# Reference_Voltage_1V65.net
KiCad netlist of a schematic drawn in Altium Designer
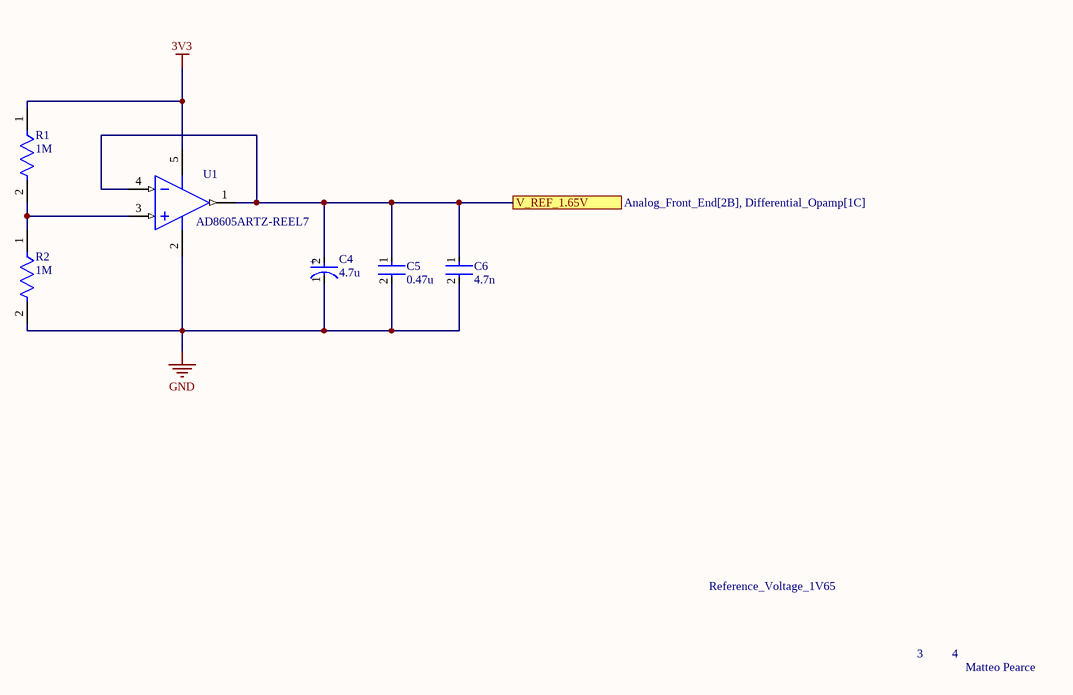
[diagram p0: Reference_Voltage_1V65.SchDoc]

(export (version "E")
  (design (tool "Eeschema 10.0.6"))
  (components
    (comp (ref "C4")
      (value "4.7u")
      (footprint "FP-TAJA-MFG")
      (description "4.7uF 20V  ±10% 4Ω 1206  SMD Tantalum Capacitor")
      (fields (field (name "TOLERANCE") "10%") (field (name "VOLTAGE") "20V"))
      (libsource (lib "Altium Content Vault") (part "203bc49f2ac43e59fd269a8c329ed05"))
    )
    (comp (ref "C5")
      (value "0.47u")
      (footprint "FP-GCM188-0_1-IPC_A")
      (description "Ceramic Capacitor for Automotive 470nF  ±10% 16VDC X7R 0603 Paper T/R")
      (fields (field (name "VOLTAGE") "16V") (field (name "TOLERANCE") "10%"))
      (libsource (lib "Altium Content Vault") (part "02cd4be3c70576c341d710602a673aa"))
    )
    (comp (ref "C6")
      (value "4.7n")
      (footprint "FP-CC0805-0_85-MFG")
      (description "CC0805 47 nF X7R 10.00% 50 V")
      (fields (field (name "MANUFACTURER PART NUMBER") "CC0805KRX7R9BB473"))
      (libsource (lib "Altium Content Vault") (part "11868f565c42a9108669ba33697ecf6"))
    )
    (comp (ref "R1")
      (value "1M")
      (footprint "FP-MCR01-IPC_B")
      (description "Thick Film Chip Resistor, 0402, 1MΩ, 0.5%, 50ppm/°C, 0.063W, 50V")
      (libsource (lib "Altium Content Vault") (part "1029c3af85768c4190bb7ad29bc67b5"))
    )
    (comp (ref "R2")
      (value "1M")
      (footprint "FP-MCR01-IPC_B")
      (description "Thick Film Chip Resistor, 0402, 1MΩ, 0.5%, 50ppm/°C, 0.063W, 50V")
      (libsource (lib "Altium Content Vault") (part "1029c3af85768c4190bb7ad29bc67b5"))
    )
    (comp (ref "U1")
      (value "AD8605ARTZ-REEL7")
      (footprint "ADI-RJ-5_M")
      (fields (field (name "MANUFACTURER") "Analog Devices") (field (name "GENERIC PART NUMBER") "AD8605"))
      (libsource (lib "Altium Content Vault") (part "ADI-ADxxxx-X-5"))
    )
  )
  (nets
    (net (code "1") (name "/V_REF_1.65V") (class "Default")
      (node (ref "C4") (pin "2") (pinfunction "A_2") (pintype "passive"))
      (node (ref "C5") (pin "1") (pinfunction "1_1") (pintype "passive"))
      (node (ref "C6") (pin "1") (pinfunction "1_1") (pintype "passive"))
      (node (ref "U1") (pin "1") (pinfunction "OUT_1") (pintype "output"))
      (node (ref "U1") (pin "4") (pinfunction "-IN_4") (pintype "input"))
    )
    (net (code "2") (name "3V3") (class "Default")
      (node (ref "R1") (pin "1") (pinfunction "1_1") (pintype "passive"))
      (node (ref "U1") (pin "5") (pinfunction "+V_5") (pintype "power_in"))
    )
    (net (code "3") (name "GND") (class "Default")
      (node (ref "C4") (pin "1") (pinfunction "C_1") (pintype "passive"))
      (node (ref "C5") (pin "2") (pinfunction "2_2") (pintype "passive"))
      (node (ref "C6") (pin "2") (pinfunction "2_2") (pintype "passive"))
      (node (ref "R2") (pin "2") (pinfunction "2_2") (pintype "passive"))
      (node (ref "U1") (pin "2") (pinfunction "-V_2") (pintype "power_in"))
    )
    (net (code "4") (name "Net-(U1-+IN)") (class "Default")
      (node (ref "R1") (pin "2") (pinfunction "2_2") (pintype "passive"))
      (node (ref "R2") (pin "1") (pinfunction "1_1") (pintype "passive"))
      (node (ref "U1") (pin "3") (pinfunction "+IN_3") (pintype "input"))
    )
  )
)
